# llrf_afe_reserve_io.net
KiCad netlist of a schematic drawn in Altium Designer
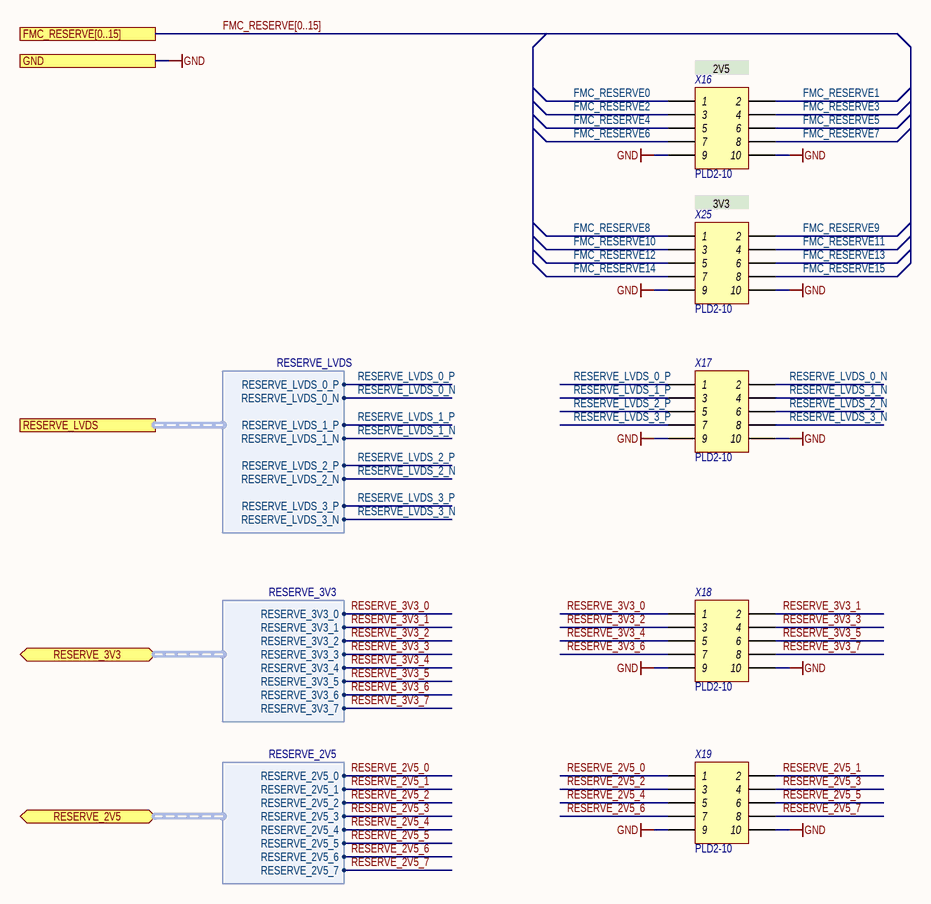
[diagram p0: llrf_afe_reserve_io.SchDoc]

(export (version "E")
  (design (tool "Eeschema 10.0.6"))
  (components
    (comp (ref "X16")
      (value "Header 2X10")
      (footprint "PLD2-10")
      (description "Header, 10-Pin, Dual row")
      (fields (field (name "НАИМЕНОВАНИЕ") "PLD2-10"))
      (libsource (lib "Connector") (part "Header 2X10"))
    )
    (comp (ref "X17")
      (value "Header 2X10")
      (footprint "PLD2-10")
      (description "Header, 10-Pin, Dual row")
      (fields (field (name "НАИМЕНОВАНИЕ") "PLD2-10"))
      (libsource (lib "Connector") (part "Header 2X10"))
    )
    (comp (ref "X18")
      (value "Header 2X10")
      (footprint "PLD2-10")
      (description "Header, 10-Pin, Dual row")
      (fields (field (name "НАИМЕНОВАНИЕ") "PLD2-10"))
      (libsource (lib "Connector") (part "Header 2X10"))
    )
    (comp (ref "X19")
      (value "Header 2X10")
      (footprint "PLD2-10")
      (description "Header, 10-Pin, Dual row")
      (fields (field (name "НАИМЕНОВАНИЕ") "PLD2-10"))
      (libsource (lib "Connector") (part "Header 2X10"))
    )
    (comp (ref "X25")
      (value "Header 2X10")
      (footprint "PLD2-10")
      (description "Header, 10-Pin, Dual row")
      (fields (field (name "НАИМЕНОВАНИЕ") "PLD2-10"))
      (libsource (lib "Connector") (part "Header 2X10"))
    )
  )
  (nets
    (net (code "4") (name "/FMC_RESERVE0") (class "Default")
      (node (ref "X16") (pin "1") (pinfunction "1_1") (pintype "passive"))
    )
    (net (code "5") (name "/FMC_RESERVE1") (class "Default")
      (node (ref "X16") (pin "2") (pinfunction "2_2") (pintype "passive"))
    )
    (net (code "6") (name "/FMC_RESERVE2") (class "Default")
      (node (ref "X16") (pin "3") (pinfunction "3_3") (pintype "passive"))
    )
    (net (code "7") (name "/FMC_RESERVE3") (class "Default")
      (node (ref "X16") (pin "4") (pinfunction "4_4") (pintype "passive"))
    )
    (net (code "8") (name "/FMC_RESERVE4") (class "Default")
      (node (ref "X16") (pin "5") (pinfunction "5_5") (pintype "passive"))
    )
    (net (code "9") (name "/FMC_RESERVE5") (class "Default")
      (node (ref "X16") (pin "6") (pinfunction "6_6") (pintype "passive"))
    )
    (net (code "10") (name "/FMC_RESERVE6") (class "Default")
      (node (ref "X16") (pin "7") (pinfunction "7_7") (pintype "passive"))
    )
    (net (code "11") (name "/FMC_RESERVE7") (class "Default")
      (node (ref "X16") (pin "8") (pinfunction "8_8") (pintype "passive"))
    )
    (net (code "12") (name "/FMC_RESERVE8") (class "Default")
      (node (ref "X25") (pin "1") (pinfunction "1_1") (pintype "passive"))
    )
    (net (code "13") (name "/FMC_RESERVE9") (class "Default")
      (node (ref "X25") (pin "2") (pinfunction "2_2") (pintype "passive"))
    )
    (net (code "14") (name "/FMC_RESERVE10") (class "Default")
      (node (ref "X25") (pin "3") (pinfunction "3_3") (pintype "passive"))
    )
    (net (code "15") (name "/FMC_RESERVE11") (class "Default")
      (node (ref "X25") (pin "4") (pinfunction "4_4") (pintype "passive"))
    )
    (net (code "16") (name "/FMC_RESERVE12") (class "Default")
      (node (ref "X25") (pin "5") (pinfunction "5_5") (pintype "passive"))
    )
    (net (code "17") (name "/FMC_RESERVE13") (class "Default")
      (node (ref "X25") (pin "6") (pinfunction "6_6") (pintype "passive"))
    )
    (net (code "18") (name "/FMC_RESERVE14") (class "Default")
      (node (ref "X25") (pin "7") (pinfunction "7_7") (pintype "passive"))
    )
    (net (code "19") (name "/FMC_RESERVE15") (class "Default")
      (node (ref "X25") (pin "8") (pinfunction "8_8") (pintype "passive"))
    )
    (net (code "21") (name "/RESERVE_2V5_0") (class "Default")
      (node (ref "X19") (pin "1") (pinfunction "1_1") (pintype "passive"))
    )
    (net (code "22") (name "/RESERVE_2V5_1") (class "Default")
      (node (ref "X19") (pin "2") (pinfunction "2_2") (pintype "passive"))
    )
    (net (code "23") (name "/RESERVE_2V5_2") (class "Default")
      (node (ref "X19") (pin "3") (pinfunction "3_3") (pintype "passive"))
    )
    (net (code "24") (name "/RESERVE_2V5_3") (class "Default")
      (node (ref "X19") (pin "4") (pinfunction "4_4") (pintype "passive"))
    )
    (net (code "25") (name "/RESERVE_2V5_4") (class "Default")
      (node (ref "X19") (pin "5") (pinfunction "5_5") (pintype "passive"))
    )
    (net (code "26") (name "/RESERVE_2V5_5") (class "Default")
      (node (ref "X19") (pin "6") (pinfunction "6_6") (pintype "passive"))
    )
    (net (code "27") (name "/RESERVE_2V5_6") (class "Default")
      (node (ref "X19") (pin "7") (pinfunction "7_7") (pintype "passive"))
    )
    (net (code "28") (name "/RESERVE_2V5_7") (class "Default")
      (node (ref "X19") (pin "8") (pinfunction "8_8") (pintype "passive"))
    )
    (net (code "29") (name "/RESERVE_3V3_0") (class "Default")
      (node (ref "X18") (pin "1") (pinfunction "1_1") (pintype "passive"))
    )
    (net (code "30") (name "/RESERVE_3V3_1") (class "Default")
      (node (ref "X18") (pin "2") (pinfunction "2_2") (pintype "passive"))
    )
    (net (code "31") (name "/RESERVE_3V3_2") (class "Default")
      (node (ref "X18") (pin "3") (pinfunction "3_3") (pintype "passive"))
    )
    (net (code "32") (name "/RESERVE_3V3_3") (class "Default")
      (node (ref "X18") (pin "4") (pinfunction "4_4") (pintype "passive"))
    )
    (net (code "33") (name "/RESERVE_3V3_4") (class "Default")
      (node (ref "X18") (pin "5") (pinfunction "5_5") (pintype "passive"))
    )
    (net (code "34") (name "/RESERVE_3V3_5") (class "Default")
      (node (ref "X18") (pin "6") (pinfunction "6_6") (pintype "passive"))
    )
    (net (code "35") (name "/RESERVE_3V3_6") (class "Default")
      (node (ref "X18") (pin "7") (pinfunction "7_7") (pintype "passive"))
    )
    (net (code "36") (name "/RESERVE_3V3_7") (class "Default")
      (node (ref "X18") (pin "8") (pinfunction "8_8") (pintype "passive"))
    )
    (net (code "37") (name "/RESERVE_LVDS_0_N") (class "Default")
      (node (ref "X17") (pin "2") (pinfunction "2_2") (pintype "passive"))
    )
    (net (code "38") (name "/RESERVE_LVDS_0_P") (class "Default")
      (node (ref "X17") (pin "1") (pinfunction "1_1") (pintype "passive"))
    )
    (net (code "39") (name "/RESERVE_LVDS_1_N") (class "Default")
      (node (ref "X17") (pin "4") (pinfunction "4_4") (pintype "passive"))
    )
    (net (code "40") (name "/RESERVE_LVDS_1_P") (class "Default")
      (node (ref "X17") (pin "3") (pinfunction "3_3") (pintype "passive"))
    )
    (net (code "41") (name "/RESERVE_LVDS_2_N") (class "Default")
      (node (ref "X17") (pin "6") (pinfunction "6_6") (pintype "passive"))
    )
    (net (code "42") (name "/RESERVE_LVDS_2_P") (class "Default")
      (node (ref "X17") (pin "5") (pinfunction "5_5") (pintype "passive"))
    )
    (net (code "43") (name "/RESERVE_LVDS_3_N") (class "Default")
      (node (ref "X17") (pin "8") (pinfunction "8_8") (pintype "passive"))
    )
    (net (code "44") (name "/RESERVE_LVDS_3_P") (class "Default")
      (node (ref "X17") (pin "7") (pinfunction "7_7") (pintype "passive"))
    )
    (net (code "48") (name "GND") (class "Default")
      (node (ref "X16") (pin "10") (pinfunction "10_10") (pintype "passive"))
      (node (ref "X16") (pin "9") (pinfunction "9_9") (pintype "passive"))
      (node (ref "X17") (pin "10") (pinfunction "10_10") (pintype "passive"))
      (node (ref "X17") (pin "9") (pinfunction "9_9") (pintype "passive"))
      (node (ref "X18") (pin "10") (pinfunction "10_10") (pintype "passive"))
      (node (ref "X18") (pin "9") (pinfunction "9_9") (pintype "passive"))
      (node (ref "X19") (pin "10") (pinfunction "10_10") (pintype "passive"))
      (node (ref "X19") (pin "9") (pinfunction "9_9") (pintype "passive"))
      (node (ref "X25") (pin "10") (pinfunction "10_10") (pintype "passive"))
      (node (ref "X25") (pin "9") (pinfunction "9_9") (pintype "passive"))
    )
  )
)
